# Power.net
KiCad netlist of a schematic drawn in Altium Designer
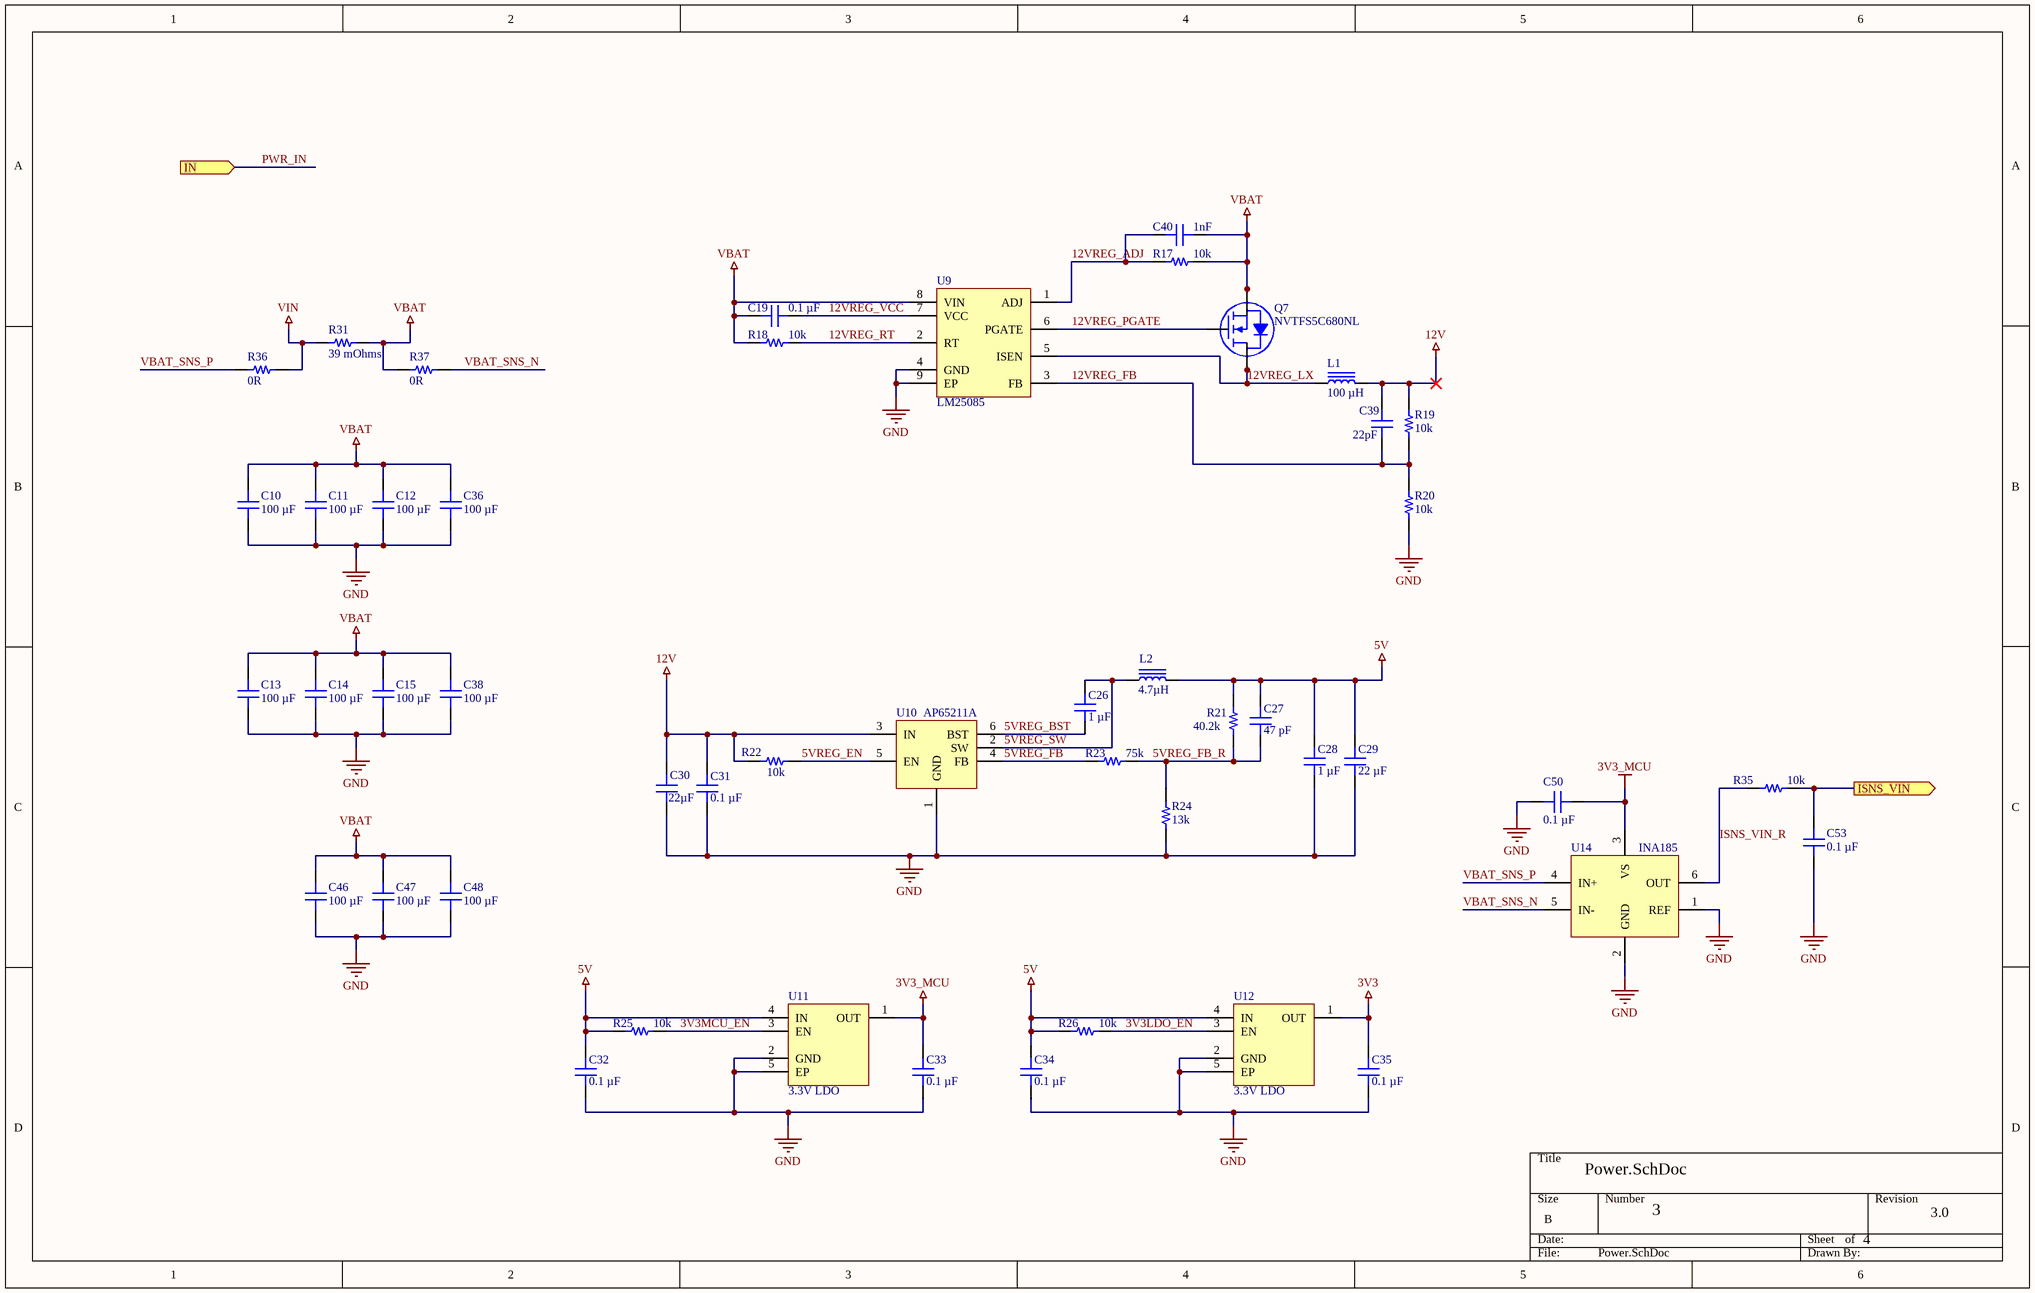
[diagram p0: Power.SchDoc]

(export (version "E")
  (design (tool "Eeschema 10.0.6"))
  (components
    (comp (ref "C10")
      (value "100 µF")
      (footprint "CAP 1210_3225 - 1MM")
      (description "CAP CER 100UF 16V X5R 1210")
      (fields (field (name "PART NUMBER") "MSASE32MAB5107MPNA01") (field (name "MANUFACTURER") "Taiyo Yuden"))
      (libsource (lib "Celestial Altium Library - altium_library") (part "Capacitor"))
    )
    (comp (ref "C11")
      (value "100 µF")
      (footprint "CAP 1210_3225 - 1MM")
      (description "CAP CER 100UF 16V X5R 1210")
      (fields (field (name "PART NUMBER") "MSASE32MAB5107MPNA01") (field (name "MANUFACTURER") "Taiyo Yuden"))
      (libsource (lib "Celestial Altium Library - altium_library") (part "Capacitor"))
    )
    (comp (ref "C12")
      (value "100 µF")
      (footprint "CAP 1210_3225 - 1MM")
      (description "CAP CER 100UF 16V X5R 1210")
      (fields (field (name "PART NUMBER") "MSASE32MAB5107MPNA01") (field (name "MANUFACTURER") "Taiyo Yuden"))
      (libsource (lib "Celestial Altium Library - altium_library") (part "Capacitor"))
    )
    (comp (ref "C13")
      (value "100 µF")
      (footprint "CAP 1210_3225 - 1MM")
      (description "CAP CER 100UF 16V X5R 1210")
      (fields (field (name "PART NUMBER") "MSASE32MAB5107MPNA01") (field (name "MANUFACTURER") "Taiyo Yuden"))
      (libsource (lib "Celestial Altium Library - altium_library") (part "Capacitor"))
    )
    (comp (ref "C14")
      (value "100 µF")
      (footprint "CAP 1210_3225 - 1MM")
      (description "CAP CER 100UF 16V X5R 1210")
      (fields (field (name "PART NUMBER") "MSASE32MAB5107MPNA01") (field (name "MANUFACTURER") "Taiyo Yuden"))
      (libsource (lib "Celestial Altium Library - altium_library") (part "Capacitor"))
    )
    (comp (ref "C15")
      (value "100 µF")
      (footprint "CAP 1210_3225 - 1MM")
      (description "CAP CER 100UF 16V X5R 1210")
      (fields (field (name "PART NUMBER") "MSASE32MAB5107MPNA01") (field (name "MANUFACTURER") "Taiyo Yuden"))
      (libsource (lib "Celestial Altium Library - altium_library") (part "Capacitor"))
    )
    (comp (ref "C19")
      (value "0.1 µF")
      (footprint "CAP 0402_1005")
      (description "CAP CER 0.1UF 16V X7R 0402")
      (fields (field (name "PART NUMBER") "C0402C104K4RACAUTO") (field (name "MANUFACTURER") "KEMET"))
      (libsource (lib "Celestial Altium Library - altium_library") (part "Capacitor"))
    )
    (comp (ref "C26")
      (value "1 µF")
      (footprint "CAP 0402_1005")
      (description "CAP CER 0.1UF 16V X7R 0402")
      (fields (field (name "PART NUMBER") "C0402C104K4RACAUTO") (field (name "MANUFACTURER") "KEMET"))
      (libsource (lib "Celestial Altium Library - altium_library") (part "Capacitor"))
    )
    (comp (ref "C27")
      (value "47 pF")
      (footprint "CAP 0402_1005")
      (description "CAP CER 0.1UF 16V X7R 0402")
      (fields (field (name "PART NUMBER") "C0402C104K4RACAUTO") (field (name "MANUFACTURER") "KEMET"))
      (libsource (lib "Celestial Altium Library - altium_library") (part "Capacitor"))
    )
    (comp (ref "C28")
      (value "1 µF")
      (footprint "CAP 0402_1005")
      (description "CAP CER 0.1UF 16V X7R 0402")
      (fields (field (name "PART NUMBER") "C0402C104K4RACAUTO") (field (name "MANUFACTURER") "KEMET"))
      (libsource (lib "Celestial Altium Library - altium_library") (part "Capacitor"))
    )
    (comp (ref "C29")
      (value "22 µF")
      (footprint "CAP 0402_1005")
      (description "CAP CER 0.1UF 16V X7R 0402")
      (fields (field (name "PART NUMBER") "C0402C104K4RACAUTO") (field (name "MANUFACTURER") "KEMET"))
      (libsource (lib "Celestial Altium Library - altium_library") (part "Capacitor"))
    )
    (comp (ref "C30")
      (value "22µF")
      (footprint "CAP 0805_2012")
      (description "CAP CER 10UF 25V X7S 0805")
      (fields
        (field (name "PART NUMBER") "C2012X7S1E106K125AC")
        (field (name "MANUFACTURER") "TDK Corporation")
      )
      (libsource (lib "Celestial Altium Library - altium_library") (part "Capacitor"))
    )
    (comp (ref "C31")
      (value "0.1 µF")
      (footprint "CAP 0402_1005")
      (description "CAP CER 0.1UF 16V X7R 0402")
      (fields (field (name "PART NUMBER") "C0402C104K4RACAUTO") (field (name "MANUFACTURER") "KEMET"))
      (libsource (lib "Celestial Altium Library - altium_library") (part "Capacitor"))
    )
    (comp (ref "C32")
      (value "0.1 µF")
      (footprint "CAP 0402_1005")
      (description "CAP CER 0.1UF 16V X7R 0402")
      (fields (field (name "PART NUMBER") "C0402C104K4RACAUTO") (field (name "MANUFACTURER") "KEMET"))
      (libsource (lib "Celestial Altium Library - altium_library") (part "Capacitor"))
    )
    (comp (ref "C33")
      (value "0.1 µF")
      (footprint "CAP 0402_1005")
      (description "CAP CER 0.1UF 16V X7R 0402")
      (fields (field (name "PART NUMBER") "C0402C104K4RACAUTO") (field (name "MANUFACTURER") "KEMET"))
      (libsource (lib "Celestial Altium Library - altium_library") (part "Capacitor"))
    )
    (comp (ref "C34")
      (value "0.1 µF")
      (footprint "CAP 0402_1005")
      (description "CAP CER 0.1UF 16V X7R 0402")
      (fields (field (name "PART NUMBER") "C0402C104K4RACAUTO") (field (name "MANUFACTURER") "KEMET"))
      (libsource (lib "Celestial Altium Library - altium_library") (part "Capacitor"))
    )
    (comp (ref "C35")
      (value "0.1 µF")
      (footprint "CAP 0402_1005")
      (description "CAP CER 0.1UF 16V X7R 0402")
      (fields (field (name "PART NUMBER") "C0402C104K4RACAUTO") (field (name "MANUFACTURER") "KEMET"))
      (libsource (lib "Celestial Altium Library - altium_library") (part "Capacitor"))
    )
    (comp (ref "C36")
      (value "100 µF")
      (footprint "CAP 1210_3225 - 1MM")
      (description "CAP CER 100UF 16V X5R 1210")
      (fields (field (name "PART NUMBER") "MSASE32MAB5107MPNA01") (field (name "MANUFACTURER") "Taiyo Yuden"))
      (libsource (lib "Celestial Altium Library - altium_library") (part "Capacitor"))
    )
    (comp (ref "C38")
      (value "100 µF")
      (footprint "CAP 1210_3225 - 1MM")
      (description "CAP CER 100UF 16V X5R 1210")
      (fields (field (name "PART NUMBER") "MSASE32MAB5107MPNA01") (field (name "MANUFACTURER") "Taiyo Yuden"))
      (libsource (lib "Celestial Altium Library - altium_library") (part "Capacitor"))
    )
    (comp (ref "C39")
      (value "22pF")
      (footprint "CAP 0402_1005")
      (description "CAP CER 0.1UF 16V X7R 0402")
      (fields (field (name "PART NUMBER") "C0402C104K4RACAUTO") (field (name "MANUFACTURER") "KEMET"))
      (libsource (lib "Celestial Altium Library - altium_library") (part "Capacitor"))
    )
    (comp (ref "C40")
      (value "1nF")
      (footprint "CAP 0402_1005")
      (description "CAP CER 0.1UF 16V X7R 0402")
      (fields (field (name "PART NUMBER") "C0402C104K4RACAUTO") (field (name "MANUFACTURER") "KEMET"))
      (libsource (lib "Celestial Altium Library - altium_library") (part "Capacitor"))
    )
    (comp (ref "C46")
      (value "100 µF")
      (footprint "CAP 1210_3225 - 1MM")
      (description "CAP CER 100UF 16V X5R 1210")
      (fields (field (name "PART NUMBER") "MSASE32MAB5107MPNA01") (field (name "MANUFACTURER") "Taiyo Yuden"))
      (libsource (lib "Celestial Altium Library - altium_library") (part "Capacitor"))
    )
    (comp (ref "C47")
      (value "100 µF")
      (footprint "CAP 1210_3225 - 1MM")
      (description "CAP CER 100UF 16V X5R 1210")
      (fields (field (name "PART NUMBER") "MSASE32MAB5107MPNA01") (field (name "MANUFACTURER") "Taiyo Yuden"))
      (libsource (lib "Celestial Altium Library - altium_library") (part "Capacitor"))
    )
    (comp (ref "C48")
      (value "100 µF")
      (footprint "CAP 1210_3225 - 1MM")
      (description "CAP CER 100UF 16V X5R 1210")
      (fields (field (name "PART NUMBER") "MSASE32MAB5107MPNA01") (field (name "MANUFACTURER") "Taiyo Yuden"))
      (libsource (lib "Celestial Altium Library - altium_library") (part "Capacitor"))
    )
    (comp (ref "C50")
      (value "0.1 µF")
      (footprint "CAP 0402_1005")
      (description "CAP CER 0.1UF 16V X7R 0402")
      (fields (field (name "PART NUMBER") "C0402C104K4RACAUTO") (field (name "MANUFACTURER") "KEMET"))
      (libsource (lib "Celestial Altium Library - altium_library") (part "Capacitor"))
    )
    (comp (ref "C53")
      (value "0.1 µF")
      (footprint "CAP 0402_1005")
      (description "CAP CER 0.1UF 16V X7R 0402")
      (fields (field (name "PART NUMBER") "C0402C104K4RACAUTO") (field (name "MANUFACTURER") "KEMET"))
      (libsource (lib "Celestial Altium Library - altium_library") (part "Capacitor"))
    )
    (comp (ref "L1")
      (value "100 µH")
      (footprint "TDK VLCF4028-2")
      (description "FIXED IND 100UH 330MA 1 OHM SMD")
      (fields
        (field (name "PART NUMBER") "VLCF4028T-101MR33-2")
        (field (name "MANUFACTURER") "TDK Corporation")
      )
      (libsource (lib "Celestial Altium Library - altium_library") (part "Inductor"))
    )
    (comp (ref "L2")
      (value "4.7µH")
      (footprint "IND 1008_2520")
      (description "FIXED IND 4.7UH 1A 110 MOHM SMD")
      (fields (field (name "PART NUMBER") "MLP2520S4R7ST0S1") (field (name "MANUFACTURER") "TDK Corporation"))
      (libsource (lib "Celestial Altium Library - altium_library") (part "Inductor"))
    )
    (comp (ref "Q7")
      (value "NVTFS5C680NL")
      (footprint "NVTFS015N04CTAG")
      (description "N-FET")
      (libsource (lib "IC") (part "NVTFS5C680NL"))
    )
    (comp (ref "R17")
      (value "10k")
      (footprint "RES 0402_1005")
      (description "RES 14.3K OHM 1% 1/10W 0402")
      (fields
        (field (name "PART NUMBER") "RK73H1ETTP1432F")
        (field (name "MANUFACTURER") "KOA Speer Electronics, Inc.")
      )
      (libsource (lib "Celestial Altium Library - altium_library") (part "Resistor"))
    )
    (comp (ref "R18")
      (value "10k")
      (footprint "RES 0402_1005")
      (description "RES 14.3K OHM 1% 1/10W 0402")
      (fields
        (field (name "PART NUMBER") "RK73H1ETTP1432F")
        (field (name "MANUFACTURER") "KOA Speer Electronics, Inc.")
      )
      (libsource (lib "Celestial Altium Library - altium_library") (part "Resistor"))
    )
    (comp (ref "R19")
      (value "10k")
      (footprint "RES 0402_1005")
      (description "RES 14.3K OHM 1% 1/10W 0402")
      (fields
        (field (name "PART NUMBER") "RK73H1ETTP1432F")
        (field (name "MANUFACTURER") "KOA Speer Electronics, Inc.")
      )
      (libsource (lib "Celestial Altium Library - altium_library") (part "Resistor"))
    )
    (comp (ref "R20")
      (value "10k")
      (footprint "RES 0402_1005")
      (description "RES 14.3K OHM 1% 1/10W 0402")
      (fields
        (field (name "PART NUMBER") "RK73H1ETTP1432F")
        (field (name "MANUFACTURER") "KOA Speer Electronics, Inc.")
      )
      (libsource (lib "Celestial Altium Library - altium_library") (part "Resistor"))
    )
    (comp (ref "R21")
      (value "40.2k")
      (footprint "RES 0402_1005")
      (description "RES 14.3K OHM 1% 1/10W 0402")
      (fields
        (field (name "PART NUMBER") "RK73H1ETTP1432F")
        (field (name "MANUFACTURER") "KOA Speer Electronics, Inc.")
      )
      (libsource (lib "Celestial Altium Library - altium_library") (part "Resistor"))
    )
    (comp (ref "R22")
      (value "10k")
      (footprint "RES 0402_1005")
      (description "RES 14.3K OHM 1% 1/10W 0402")
      (fields
        (field (name "PART NUMBER") "RK73H1ETTP1432F")
        (field (name "MANUFACTURER") "KOA Speer Electronics, Inc.")
      )
      (libsource (lib "Celestial Altium Library - altium_library") (part "Resistor"))
    )
    (comp (ref "R23")
      (value "75k")
      (footprint "RES 0402_1005")
      (description "RES 14.3K OHM 1% 1/10W 0402")
      (fields
        (field (name "PART NUMBER") "RK73H1ETTP1432F")
        (field (name "MANUFACTURER") "KOA Speer Electronics, Inc.")
      )
      (libsource (lib "Celestial Altium Library - altium_library") (part "Resistor"))
    )
    (comp (ref "R24")
      (value "13k")
      (footprint "RES 0402_1005")
      (description "RES 14.3K OHM 1% 1/10W 0402")
      (fields
        (field (name "PART NUMBER") "RK73H1ETTP1432F")
        (field (name "MANUFACTURER") "KOA Speer Electronics, Inc.")
      )
      (libsource (lib "Celestial Altium Library - altium_library") (part "Resistor"))
    )
    (comp (ref "R25")
      (value "10k")
      (footprint "RES 0402_1005")
      (description "RES 14.3K OHM 1% 1/10W 0402")
      (fields
        (field (name "PART NUMBER") "RK73H1ETTP1432F")
        (field (name "MANUFACTURER") "KOA Speer Electronics, Inc.")
      )
      (libsource (lib "Celestial Altium Library - altium_library") (part "Resistor"))
    )
    (comp (ref "R26")
      (value "10k")
      (footprint "RES 0402_1005")
      (description "RES 14.3K OHM 1% 1/10W 0402")
      (fields
        (field (name "PART NUMBER") "RK73H1ETTP1432F")
        (field (name "MANUFACTURER") "KOA Speer Electronics, Inc.")
      )
      (libsource (lib "Celestial Altium Library - altium_library") (part "Resistor"))
    )
    (comp (ref "R31")
      (value "39 mOhms")
      (footprint "RES 1206_3216")
      (description "RES 0.039 OHM 1% 3/4W 1206")
      (fields (field (name "PART NUMBER") "KRL1632E-M-R039-F-T5") (field (name "MANUFACTURER") "Susumu"))
      (libsource (lib "Celestial Altium Library - altium_library") (part "Resistor"))
    )
    (comp (ref "R35")
      (value "10k")
      (footprint "RES 0402_1005")
      (description "RES 14.3K OHM 1% 1/10W 0402")
      (fields
        (field (name "PART NUMBER") "RK73H1ETTP1432F")
        (field (name "MANUFACTURER") "KOA Speer Electronics, Inc.")
      )
      (libsource (lib "Celestial Altium Library - altium_library") (part "Resistor"))
    )
    (comp (ref "R36")
      (value "0R")
      (footprint "RES 0201_0603")
      (description "RES SMD 10 OHM 1% 1/20W 0201")
      (fields
        (field (name "PART NUMBER") "CRG0201F10R")
        (field (name "MANUFACTURER") "TE Connectivity Passive Product")
      )
      (libsource (lib "Celestial Altium Library - altium_library") (part "Resistor"))
    )
    (comp (ref "R37")
      (value "0R")
      (footprint "RES 0201_0603")
      (description "RES SMD 10 OHM 1% 1/20W 0201")
      (fields
        (field (name "PART NUMBER") "CRG0201F10R")
        (field (name "MANUFACTURER") "TE Connectivity Passive Product")
      )
      (libsource (lib "Celestial Altium Library - altium_library") (part "Resistor"))
    )
    (comp (ref "U9")
      (value "LM25085")
      (footprint "8_WSON_3x3_0.5mm")
      (description "PFET Buck Controller")
      (libsource (lib "IC") (part "LM25085"))
    )
    (comp (ref "U10")
      (value "AP65211A")
      (footprint "TSOT-26-6")
      (description "ADJ step down Buck")
      (libsource (lib "IC") (part "AP65211A"))
    )
    (comp (ref "U11") (value "3.3V LDO") (footprint "XDFN-4") (libsource (lib "IC") (part "TLV74033PDQNR")))
    (comp (ref "U12") (value "3.3V LDO") (footprint "XDFN-4") (libsource (lib "IC") (part "TLV74033PDQNR")))
    (comp (ref "U14")
      (value "INA185")
      (footprint "TI SC70-6 DCK")
      (description "INA185A2")
      (libsource (lib "IC") (part "INA185"))
    )
  )
  (nets
    (net (code "1") (name "/3V3LDO_EN") (class "Default")
      (node (ref "R26") (pin "2") (pinfunction "2_2") (pintype "passive"))
      (node (ref "U12") (pin "3") (pinfunction "EN_3") (pintype "passive"))
    )
    (net (code "2") (name "/3V3MCU_EN") (class "Default")
      (node (ref "R25") (pin "2") (pinfunction "2_2") (pintype "passive"))
      (node (ref "U11") (pin "3") (pinfunction "EN_3") (pintype "passive"))
    )
    (net (code "3") (name "/5VREG_BST") (class "Default")
      (node (ref "C26") (pin "1") (pinfunction "1_1") (pintype "passive"))
      (node (ref "U10") (pin "6") (pinfunction "BST_6") (pintype "passive"))
    )
    (net (code "4") (name "/5VREG_EN") (class "Default")
      (node (ref "R22") (pin "2") (pinfunction "2_2") (pintype "passive"))
      (node (ref "U10") (pin "5") (pinfunction "EN_5") (pintype "passive"))
    )
    (net (code "5") (name "/5VREG_FB") (class "Default")
      (node (ref "R23") (pin "1") (pinfunction "1_1") (pintype "passive"))
      (node (ref "U10") (pin "4") (pinfunction "FB_4") (pintype "passive"))
    )
    (net (code "6") (name "/5VREG_FB_R") (class "Default")
      (node (ref "C27") (pin "1") (pinfunction "1_1") (pintype "passive"))
      (node (ref "R21") (pin "1") (pinfunction "1_1") (pintype "passive"))
      (node (ref "R23") (pin "2") (pinfunction "2_2") (pintype "passive"))
      (node (ref "R24") (pin "2") (pinfunction "2_2") (pintype "passive"))
    )
    (net (code "7") (name "/5VREG_SW") (class "Default")
      (node (ref "C26") (pin "2") (pinfunction "2_2") (pintype "passive"))
      (node (ref "L2") (pin "1") (pinfunction "1_1") (pintype "passive"))
      (node (ref "U10") (pin "2") (pinfunction "SW_2") (pintype "passive"))
    )
    (net (code "8") (name "/12VREG_ADJ") (class "Default")
      (node (ref "C40") (pin "1") (pinfunction "1_1") (pintype "passive"))
      (node (ref "R17") (pin "1") (pinfunction "1_1") (pintype "passive"))
      (node (ref "U9") (pin "1") (pinfunction "ADJ_1") (pintype "passive"))
    )
    (net (code "9") (name "/12VREG_FB") (class "Default")
      (node (ref "C39") (pin "1") (pinfunction "1_1") (pintype "passive"))
      (node (ref "R19") (pin "1") (pinfunction "1_1") (pintype "passive"))
      (node (ref "R20") (pin "2") (pinfunction "2_2") (pintype "passive"))
      (node (ref "U9") (pin "3") (pinfunction "FB_3") (pintype "passive"))
    )
    (net (code "10") (name "/12VREG_LX") (class "Default")
      (node (ref "L1") (pin "1") (pinfunction "1_1") (pintype "passive"))
      (node (ref "Q7") (pin "5") (pinfunction "D_5") (pintype "passive"))
      (node (ref "Q7") (pin "6") (pinfunction "D_6") (pintype "passive"))
      (node (ref "Q7") (pin "7") (pinfunction "D_7") (pintype "passive"))
      (node (ref "Q7") (pin "8") (pinfunction "D_8") (pintype "passive"))
      (node (ref "U9") (pin "5") (pinfunction "ISEN_5") (pintype "passive"))
    )
    (net (code "11") (name "/12VREG_PGATE") (class "Default")
      (node (ref "Q7") (pin "4") (pinfunction "G_4") (pintype "passive"))
      (node (ref "U9") (pin "6") (pinfunction "PGATE_6") (pintype "passive"))
    )
    (net (code "12") (name "/12VREG_RT") (class "Default")
      (node (ref "R18") (pin "2") (pinfunction "2_2") (pintype "passive"))
      (node (ref "U9") (pin "2") (pinfunction "RT_2") (pintype "passive"))
    )
    (net (code "13") (name "/12VREG_VCC") (class "Default")
      (node (ref "C19") (pin "2") (pinfunction "2_2") (pintype "passive"))
      (node (ref "U9") (pin "7") (pinfunction "VCC_7") (pintype "passive"))
    )
    (net (code "14") (name "/ISNS_VIN") (class "Default")
      (node (ref "C53") (pin "1") (pinfunction "1_1") (pintype "passive"))
      (node (ref "R35") (pin "2") (pinfunction "2_2") (pintype "passive"))
    )
    (net (code "15") (name "/ISNS_VIN_R") (class "Default")
      (node (ref "R35") (pin "1") (pinfunction "1_1") (pintype "passive"))
      (node (ref "U14") (pin "6") (pinfunction "OUT_6") (pintype "passive"))
    )
    (net (code "17") (name "/VBAT_SNS_N") (class "Default")
      (node (ref "R37") (pin "2") (pinfunction "2_2") (pintype "passive"))
      (node (ref "U14") (pin "5") (pinfunction "IN-_5") (pintype "passive"))
    )
    (net (code "18") (name "/VBAT_SNS_P") (class "Default")
      (node (ref "R36") (pin "1") (pinfunction "1_1") (pintype "passive"))
      (node (ref "U14") (pin "4") (pinfunction "IN+_4") (pintype "passive"))
    )
    (net (code "19") (name "3V3") (class "Default")
      (node (ref "C35") (pin "2") (pinfunction "2_2") (pintype "passive"))
      (node (ref "U12") (pin "1") (pinfunction "OUT_1") (pintype "passive"))
    )
    (net (code "20") (name "3V3_MCU") (class "Default")
      (node (ref "C33") (pin "2") (pinfunction "2_2") (pintype "passive"))
      (node (ref "C50") (pin "1") (pinfunction "1_1") (pintype "passive"))
      (node (ref "U11") (pin "1") (pinfunction "OUT_1") (pintype "passive"))
      (node (ref "U14") (pin "3") (pinfunction "VS_3") (pintype "passive"))
    )
    (net (code "21") (name "5V") (class "Default")
      (node (ref "C27") (pin "2") (pinfunction "2_2") (pintype "passive"))
      (node (ref "C28") (pin "2") (pinfunction "2_2") (pintype "passive"))
      (node (ref "C29") (pin "2") (pinfunction "2_2") (pintype "passive"))
      (node (ref "C32") (pin "2") (pinfunction "2_2") (pintype "passive"))
      (node (ref "C34") (pin "2") (pinfunction "2_2") (pintype "passive"))
      (node (ref "L2") (pin "2") (pinfunction "2_2") (pintype "passive"))
      (node (ref "R21") (pin "2") (pinfunction "2_2") (pintype "passive"))
      (node (ref "R25") (pin "1") (pinfunction "1_1") (pintype "passive"))
      (node (ref "R26") (pin "1") (pinfunction "1_1") (pintype "passive"))
      (node (ref "U11") (pin "4") (pinfunction "IN_4") (pintype "passive"))
      (node (ref "U12") (pin "4") (pinfunction "IN_4") (pintype "passive"))
    )
    (net (code "22") (name "12V") (class "Default")
      (node (ref "C30") (pin "2") (pinfunction "2_2") (pintype "passive"))
      (node (ref "C31") (pin "2") (pinfunction "2_2") (pintype "passive"))
      (node (ref "C39") (pin "2") (pinfunction "2_2") (pintype "passive"))
      (node (ref "L1") (pin "2") (pinfunction "2_2") (pintype "passive"))
      (node (ref "R19") (pin "2") (pinfunction "2_2") (pintype "passive"))
      (node (ref "R22") (pin "1") (pinfunction "1_1") (pintype "passive"))
      (node (ref "U10") (pin "3") (pinfunction "IN_3") (pintype "passive"))
    )
    (net (code "23") (name "GND") (class "Default")
      (node (ref "C10") (pin "1") (pinfunction "1_1") (pintype "passive"))
      (node (ref "C11") (pin "1") (pinfunction "1_1") (pintype "passive"))
      (node (ref "C12") (pin "1") (pinfunction "1_1") (pintype "passive"))
      (node (ref "C13") (pin "1") (pinfunction "1_1") (pintype "passive"))
      (node (ref "C14") (pin "1") (pinfunction "1_1") (pintype "passive"))
      (node (ref "C15") (pin "1") (pinfunction "1_1") (pintype "passive"))
      (node (ref "C28") (pin "1") (pinfunction "1_1") (pintype "passive"))
      (node (ref "C29") (pin "1") (pinfunction "1_1") (pintype "passive"))
      (node (ref "C30") (pin "1") (pinfunction "1_1") (pintype "passive"))
      (node (ref "C31") (pin "1") (pinfunction "1_1") (pintype "passive"))
      (node (ref "C32") (pin "1") (pinfunction "1_1") (pintype "passive"))
      (node (ref "C33") (pin "1") (pinfunction "1_1") (pintype "passive"))
      (node (ref "C34") (pin "1") (pinfunction "1_1") (pintype "passive"))
      (node (ref "C35") (pin "1") (pinfunction "1_1") (pintype "passive"))
      (node (ref "C36") (pin "1") (pinfunction "1_1") (pintype "passive"))
      (node (ref "C38") (pin "1") (pinfunction "1_1") (pintype "passive"))
      (node (ref "C46") (pin "1") (pinfunction "1_1") (pintype "passive"))
      (node (ref "C47") (pin "1") (pinfunction "1_1") (pintype "passive"))
      (node (ref "C48") (pin "1") (pinfunction "1_1") (pintype "passive"))
      (node (ref "C50") (pin "2") (pinfunction "2_2") (pintype "passive"))
      (node (ref "C53") (pin "2") (pinfunction "2_2") (pintype "passive"))
      (node (ref "R20") (pin "1") (pinfunction "1_1") (pintype "passive"))
      (node (ref "R24") (pin "1") (pinfunction "1_1") (pintype "passive"))
      (node (ref "U10") (pin "1") (pinfunction "GND_1") (pintype "passive"))
      (node (ref "U11") (pin "2") (pinfunction "GND_2") (pintype "passive"))
      (node (ref "U11") (pin "5") (pinfunction "EP_5") (pintype "passive"))
      (node (ref "U12") (pin "2") (pinfunction "GND_2") (pintype "passive"))
      (node (ref "U12") (pin "5") (pinfunction "EP_5") (pintype "passive"))
      (node (ref "U14") (pin "1") (pinfunction "REF_1") (pintype "passive"))
      (node (ref "U14") (pin "2") (pinfunction "GND_2") (pintype "passive"))
      (node (ref "U9") (pin "4") (pinfunction "GND_4") (pintype "passive"))
      (node (ref "U9") (pin "9") (pinfunction "EP_9") (pintype "passive"))
    )
    (net (code "24") (name "VBAT") (class "Default")
      (node (ref "C10") (pin "2") (pinfunction "2_2") (pintype "passive"))
      (node (ref "C11") (pin "2") (pinfunction "2_2") (pintype "passive"))
      (node (ref "C12") (pin "2") (pinfunction "2_2") (pintype "passive"))
      (node (ref "C13") (pin "2") (pinfunction "2_2") (pintype "passive"))
      (node (ref "C14") (pin "2") (pinfunction "2_2") (pintype "passive"))
      (node (ref "C15") (pin "2") (pinfunction "2_2") (pintype "passive"))
      (node (ref "C19") (pin "1") (pinfunction "1_1") (pintype "passive"))
      (node (ref "C36") (pin "2") (pinfunction "2_2") (pintype "passive"))
      (node (ref "C38") (pin "2") (pinfunction "2_2") (pintype "passive"))
      (node (ref "C40") (pin "2") (pinfunction "2_2") (pintype "passive"))
      (node (ref "C46") (pin "2") (pinfunction "2_2") (pintype "passive"))
      (node (ref "C47") (pin "2") (pinfunction "2_2") (pintype "passive"))
      (node (ref "C48") (pin "2") (pinfunction "2_2") (pintype "passive"))
      (node (ref "Q7") (pin "1") (pinfunction "S_1") (pintype "passive"))
      (node (ref "Q7") (pin "2") (pinfunction "S_2") (pintype "passive"))
      (node (ref "Q7") (pin "3") (pinfunction "S_3") (pintype "passive"))
      (node (ref "R17") (pin "2") (pinfunction "2_2") (pintype "passive"))
      (node (ref "R18") (pin "1") (pinfunction "1_1") (pintype "passive"))
      (node (ref "R31") (pin "2") (pinfunction "2_2") (pintype "passive"))
      (node (ref "R37") (pin "1") (pinfunction "1_1") (pintype "passive"))
      (node (ref "U9") (pin "8") (pinfunction "VIN_8") (pintype "passive"))
    )
    (net (code "25") (name "VIN") (class "Default")
      (node (ref "R31") (pin "1") (pinfunction "1_1") (pintype "passive"))
      (node (ref "R36") (pin "2") (pinfunction "2_2") (pintype "passive"))
    )
  )
)
